# Sheet1.net
KiCad netlist of a schematic drawn in Altium Designer
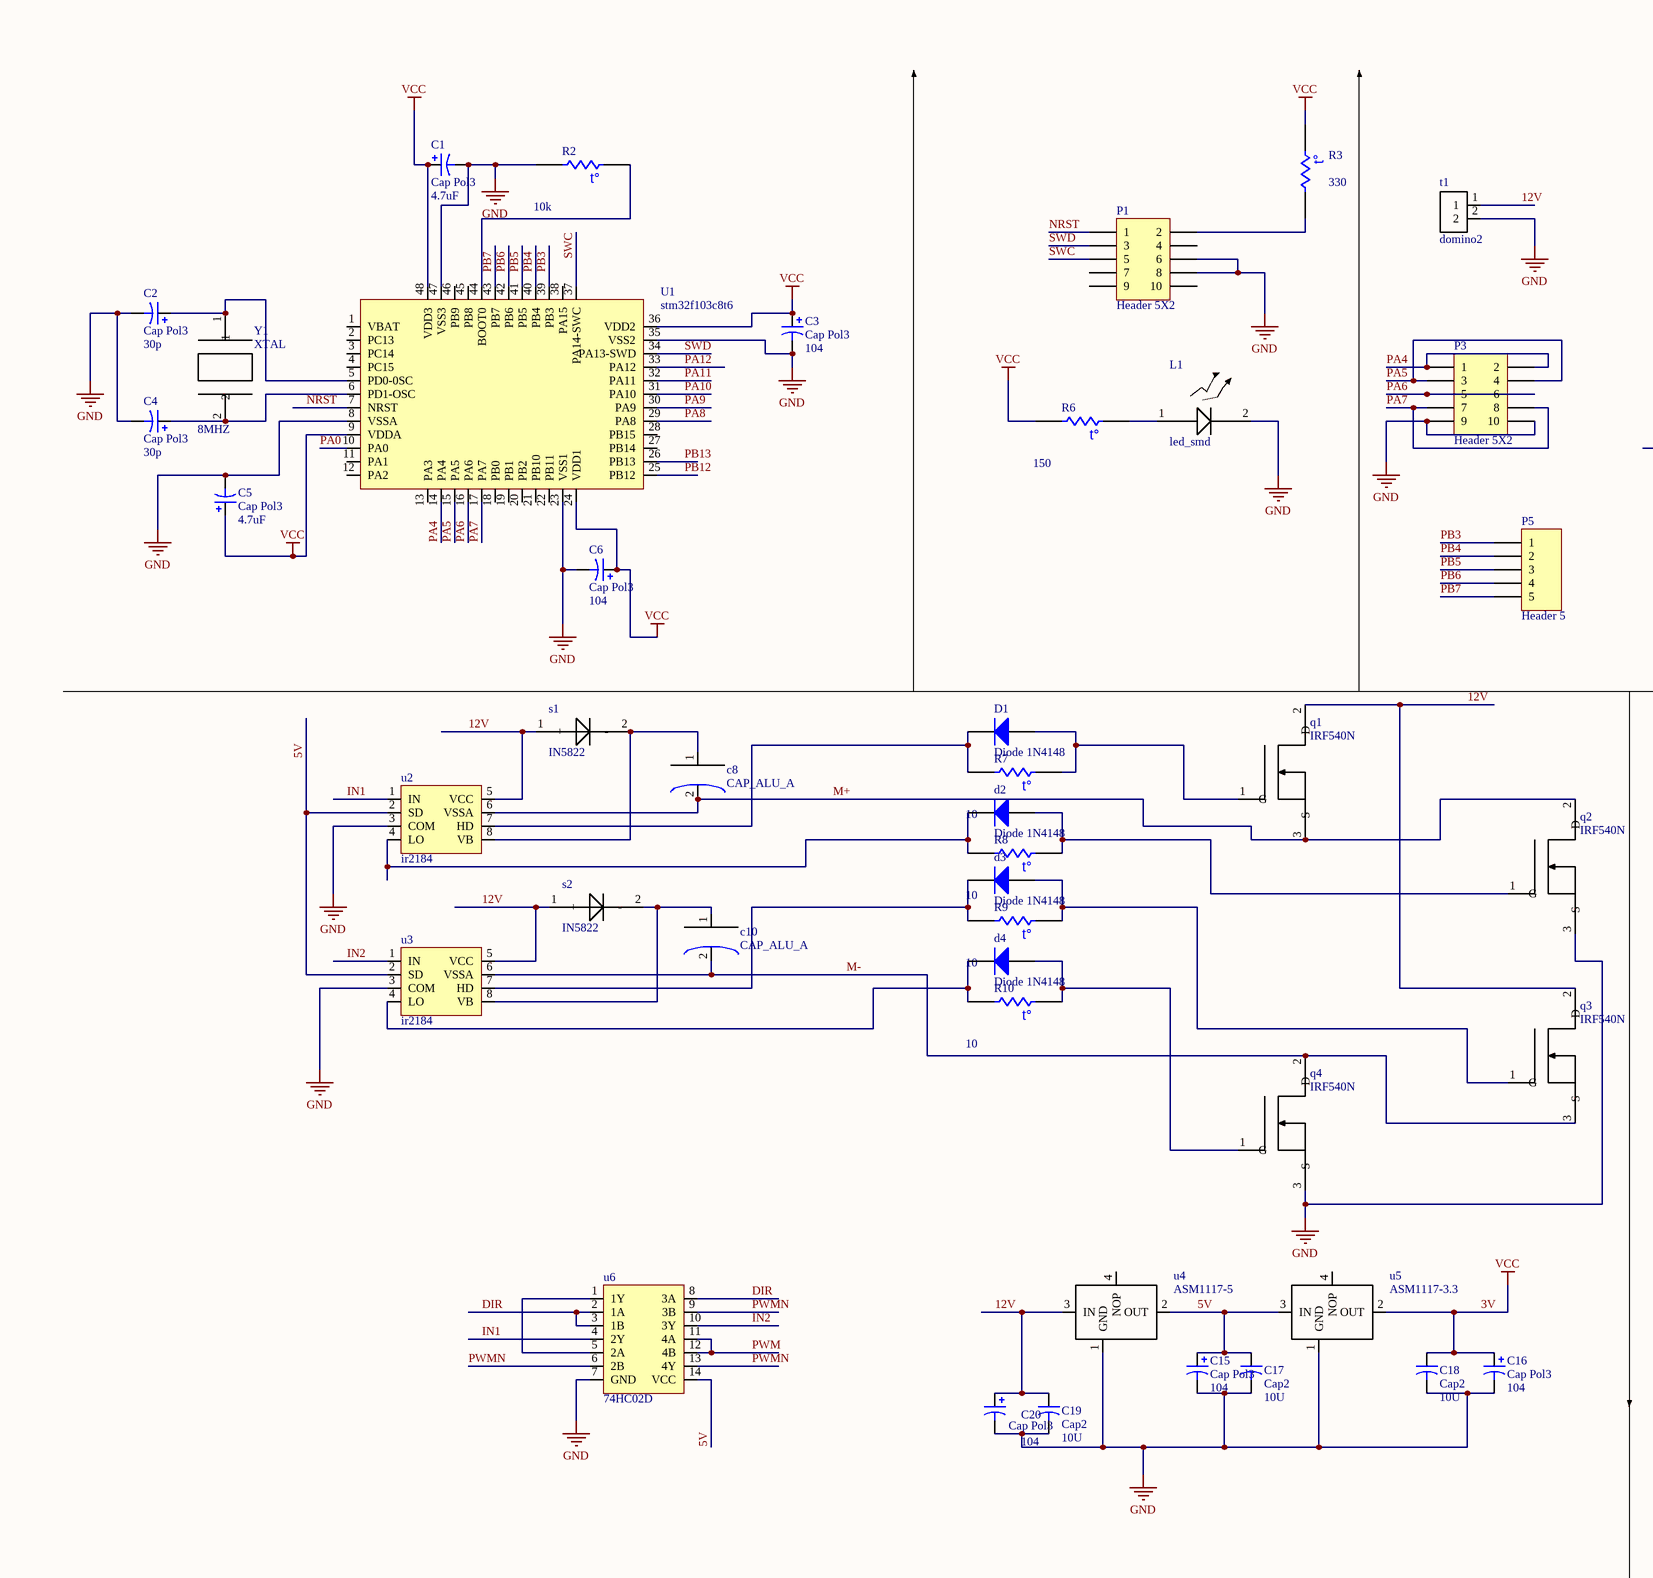
[diagram p0: Sheet1.SchDoc, left]
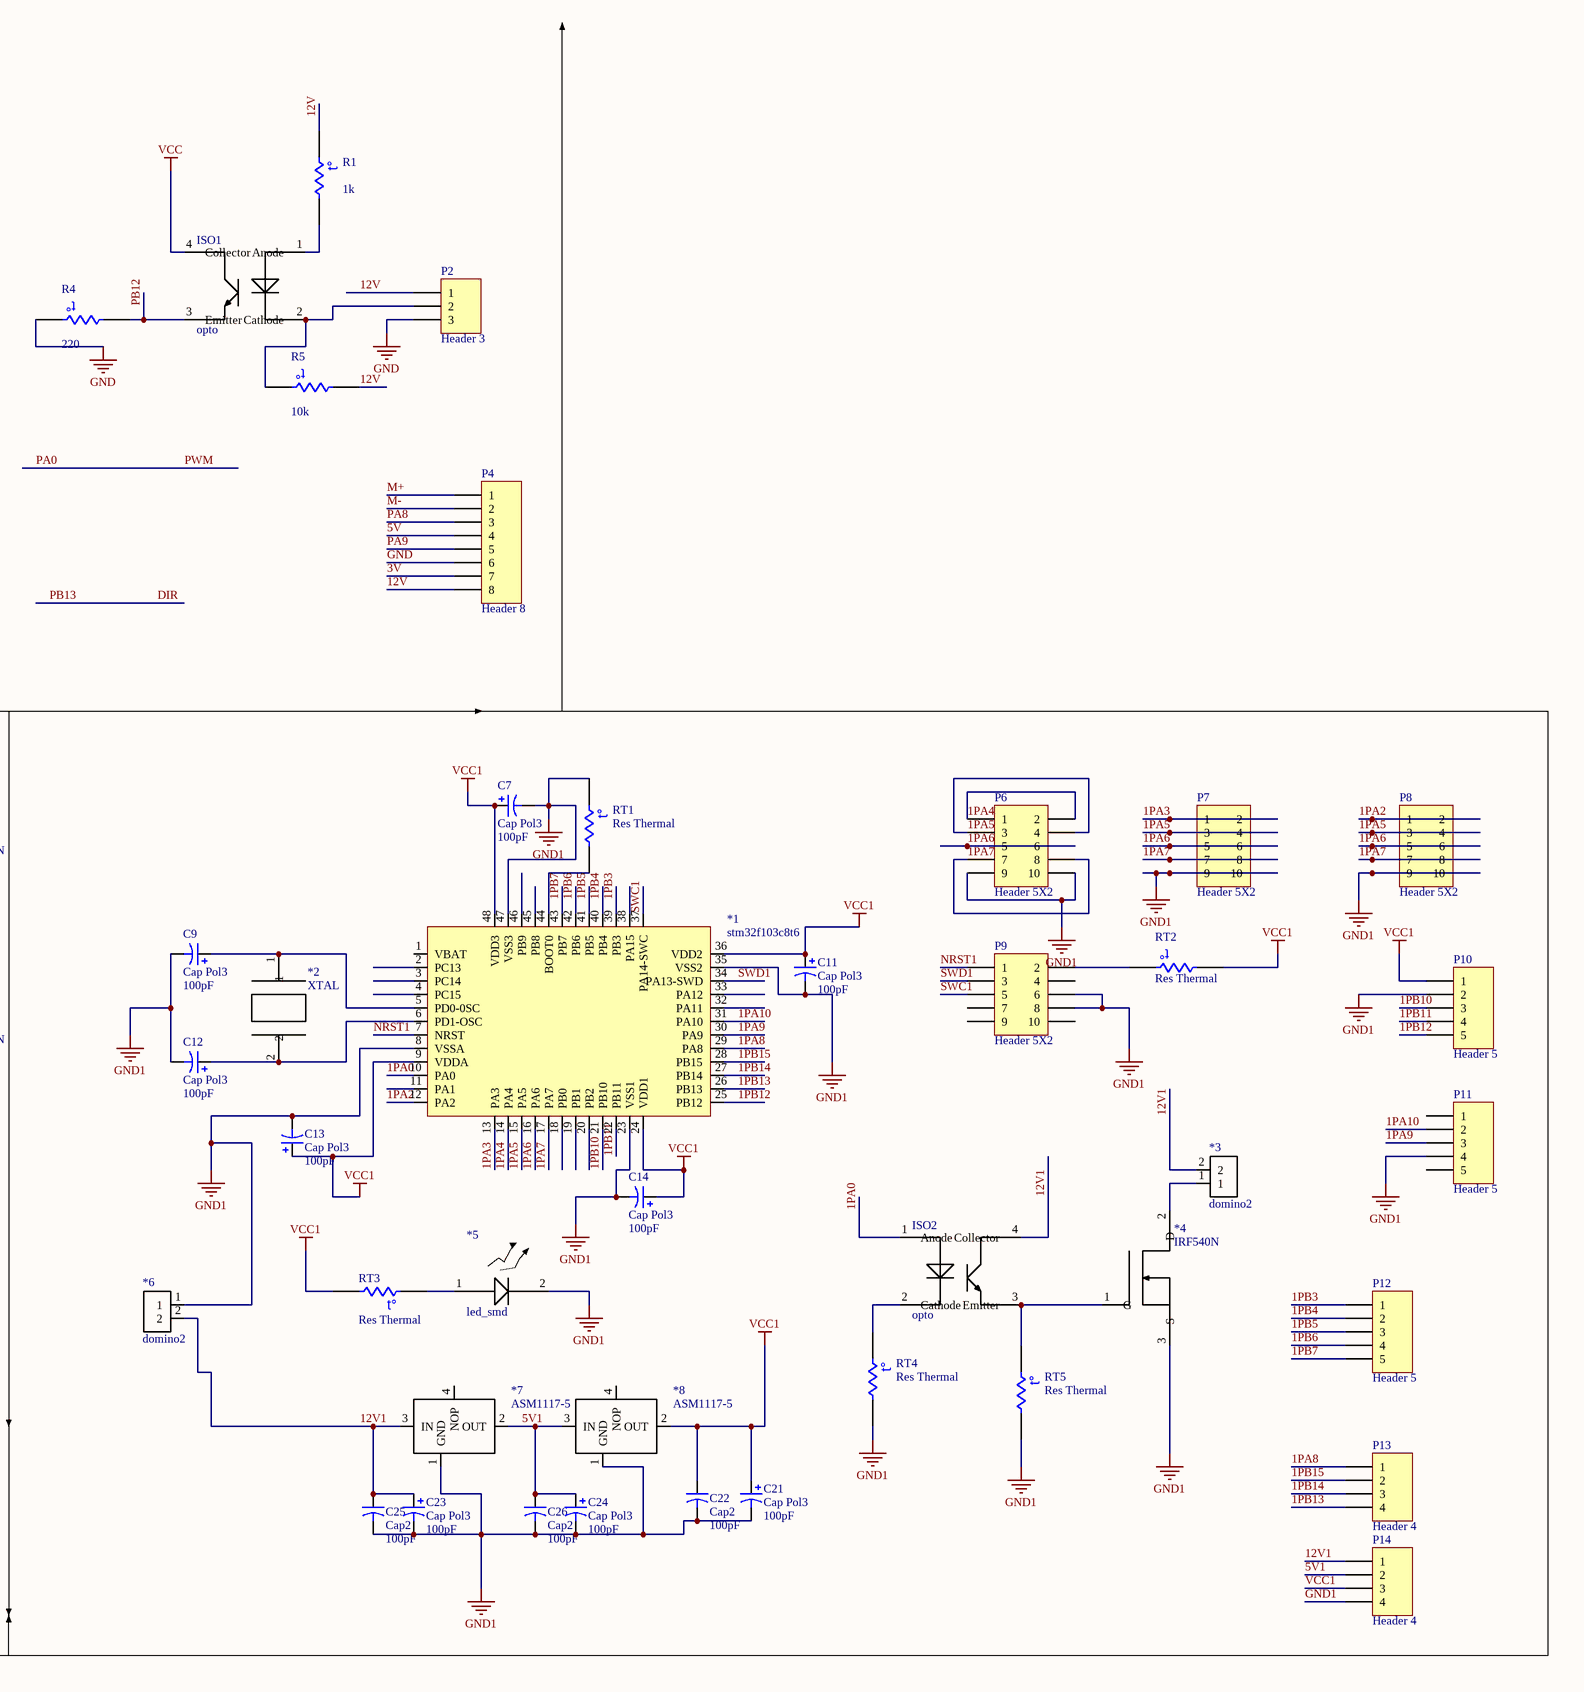
[diagram p1: Sheet1.SchDoc, right]

(export (version "E")
  (design (tool "Eeschema 10.0.6"))
  (components
    (comp (ref "*1")
      (value "stm32f103c8t6")
      (footprint "Pcbforslave:LQFP48_stm32")
      (libsource (lib "Schlib1") (part "stm32f103c8t6"))
    )
    (comp (ref "*2")
      (value "XTAL")
      (footprint "Pcbforslave:xtal_smd")
      (libsource (lib "Schlib1") (part "XTAL"))
    )
    (comp (ref "*3")
      (value "domino2")
      (footprint "Pcbforslave:Domino_2")
      (libsource (lib "Schlib1") (part "domino2"))
    )
    (comp (ref "*4")
      (value "IRF540N")
      (footprint "Pcbforslave:TO220")
      (libsource (lib "Schlib1") (part "IRF540N"))
    )
    (comp (ref "*5")
      (value "led_smd")
      (footprint "Pcbforslave:led_smd")
      (libsource (lib "Schlib1") (part "led_smd"))
    )
    (comp (ref "*6")
      (value "domino2")
      (footprint "Pcbforslave:Domino_2")
      (libsource (lib "Schlib1") (part "domino2"))
    )
    (comp (ref "*7")
      (value "ASM1117-5")
      (footprint "Pcbforslave:SOT223")
      (libsource (lib "Schlib1") (part "ASM1117-5"))
    )
    (comp (ref "*8")
      (value "ASM1117-5")
      (footprint "Pcbforslave:SOT223")
      (libsource (lib "Schlib1") (part "ASM1117-5"))
    )
    (comp (ref "C1")
      (value "Cap Pol3")
      (footprint "C0805")
      (description "Polarized Capacitor (Surface Mount)")
      (fields (field (name "ALTIUM_VALUE") "4.7uF"))
      (libsource (lib "Miscellaneous Devices") (part "Cap Pol3"))
    )
    (comp (ref "C2")
      (value "Cap Pol3")
      (footprint "C0805")
      (description "Polarized Capacitor (Surface Mount)")
      (fields (field (name "ALTIUM_VALUE") "30p"))
      (libsource (lib "Miscellaneous Devices") (part "Cap Pol3"))
    )
    (comp (ref "C3")
      (value "Cap Pol3")
      (footprint "C0805")
      (description "Polarized Capacitor (Surface Mount)")
      (fields (field (name "ALTIUM_VALUE") "104"))
      (libsource (lib "Miscellaneous Devices") (part "Cap Pol3"))
    )
    (comp (ref "C4")
      (value "Cap Pol3")
      (footprint "C0805")
      (description "Polarized Capacitor (Surface Mount)")
      (fields (field (name "ALTIUM_VALUE") "30p"))
      (libsource (lib "Miscellaneous Devices") (part "Cap Pol3"))
    )
    (comp (ref "C5")
      (value "Cap Pol3")
      (footprint "C0805")
      (description "Polarized Capacitor (Surface Mount)")
      (fields (field (name "ALTIUM_VALUE") "4.7uF"))
      (libsource (lib "Miscellaneous Devices") (part "Cap Pol3"))
    )
    (comp (ref "C6")
      (value "Cap Pol3")
      (footprint "C0805")
      (description "Polarized Capacitor (Surface Mount)")
      (fields (field (name "ALTIUM_VALUE") "104"))
      (libsource (lib "Miscellaneous Devices") (part "Cap Pol3"))
    )
    (comp (ref "C7")
      (value "Cap Pol3")
      (footprint "C0805")
      (description "Polarized Capacitor (Surface Mount)")
      (fields (field (name "ALTIUM_VALUE") "100pF"))
      (libsource (lib "Miscellaneous Devices") (part "Cap Pol3"))
    )
    (comp (ref "c8")
      (value "CAP_ALU_A")
      (footprint "cap_alu_a")
      (libsource (lib "Schlib1") (part "CAP_ALU_A"))
    )
    (comp (ref "C9")
      (value "Cap Pol3")
      (footprint "C0805")
      (description "Polarized Capacitor (Surface Mount)")
      (fields (field (name "ALTIUM_VALUE") "100pF"))
      (libsource (lib "Miscellaneous Devices") (part "Cap Pol3"))
    )
    (comp (ref "c10")
      (value "CAP_ALU_A")
      (footprint "cap_alu_a")
      (libsource (lib "Schlib1") (part "CAP_ALU_A"))
    )
    (comp (ref "C11")
      (value "Cap Pol3")
      (footprint "C0805")
      (description "Polarized Capacitor (Surface Mount)")
      (fields (field (name "ALTIUM_VALUE") "100pF"))
      (libsource (lib "Miscellaneous Devices") (part "Cap Pol3"))
    )
    (comp (ref "C12")
      (value "Cap Pol3")
      (footprint "C0805")
      (description "Polarized Capacitor (Surface Mount)")
      (fields (field (name "ALTIUM_VALUE") "100pF"))
      (libsource (lib "Miscellaneous Devices") (part "Cap Pol3"))
    )
    (comp (ref "C13")
      (value "Cap Pol3")
      (footprint "C0805")
      (description "Polarized Capacitor (Surface Mount)")
      (fields (field (name "ALTIUM_VALUE") "100pF"))
      (libsource (lib "Miscellaneous Devices") (part "Cap Pol3"))
    )
    (comp (ref "C14")
      (value "Cap Pol3")
      (footprint "C0805")
      (description "Polarized Capacitor (Surface Mount)")
      (fields (field (name "ALTIUM_VALUE") "100pF"))
      (libsource (lib "Miscellaneous Devices") (part "Cap Pol3"))
    )
    (comp (ref "C15")
      (value "Cap Pol3")
      (footprint "C0805")
      (description "Polarized Capacitor (Surface Mount)")
      (fields (field (name "ALTIUM_VALUE") "104"))
      (libsource (lib "Miscellaneous Devices") (part "Cap Pol3"))
    )
    (comp (ref "C16")
      (value "Cap Pol3")
      (footprint "C0805")
      (description "Polarized Capacitor (Surface Mount)")
      (fields (field (name "ALTIUM_VALUE") "104"))
      (libsource (lib "Miscellaneous Devices") (part "Cap Pol3"))
    )
    (comp (ref "C17")
      (value "Cap2")
      (footprint "CAPR5-4X5")
      (description "Capacitor")
      (fields (field (name "ALTIUM_VALUE") "10U"))
      (libsource (lib "Miscellaneous Devices") (part "Cap2"))
    )
    (comp (ref "C18")
      (value "Cap2")
      (footprint "CAPR5-4X5")
      (description "Capacitor")
      (fields (field (name "ALTIUM_VALUE") "10U"))
      (libsource (lib "Miscellaneous Devices") (part "Cap2"))
    )
    (comp (ref "C19")
      (value "Cap2")
      (footprint "CAPR5-4X5")
      (description "Capacitor")
      (fields (field (name "ALTIUM_VALUE") "10U"))
      (libsource (lib "Miscellaneous Devices") (part "Cap2"))
    )
    (comp (ref "C20")
      (value "Cap Pol3")
      (footprint "C0805")
      (description "Polarized Capacitor (Surface Mount)")
      (fields (field (name "ALTIUM_VALUE") "104"))
      (libsource (lib "Miscellaneous Devices") (part "Cap Pol3"))
    )
    (comp (ref "C21")
      (value "Cap Pol3")
      (footprint "C0805")
      (description "Polarized Capacitor (Surface Mount)")
      (fields (field (name "ALTIUM_VALUE") "100pF"))
      (libsource (lib "Miscellaneous Devices") (part "Cap Pol3"))
    )
    (comp (ref "C22")
      (value "Cap2")
      (footprint "CAPR5-4X5")
      (description "Capacitor")
      (fields (field (name "ALTIUM_VALUE") "100pF"))
      (libsource (lib "Miscellaneous Devices") (part "Cap2"))
    )
    (comp (ref "C23")
      (value "Cap Pol3")
      (footprint "C0805")
      (description "Polarized Capacitor (Surface Mount)")
      (fields (field (name "ALTIUM_VALUE") "100pF"))
      (libsource (lib "Miscellaneous Devices") (part "Cap Pol3"))
    )
    (comp (ref "C24")
      (value "Cap Pol3")
      (footprint "C0805")
      (description "Polarized Capacitor (Surface Mount)")
      (fields (field (name "ALTIUM_VALUE") "100pF"))
      (libsource (lib "Miscellaneous Devices") (part "Cap Pol3"))
    )
    (comp (ref "C25")
      (value "Cap2")
      (footprint "CAPR5-4X5")
      (description "Capacitor")
      (fields (field (name "ALTIUM_VALUE") "100pF"))
      (libsource (lib "Miscellaneous Devices") (part "Cap2"))
    )
    (comp (ref "C26")
      (value "Cap2")
      (footprint "CAPR5-4X5")
      (description "Capacitor")
      (fields (field (name "ALTIUM_VALUE") "100pF"))
      (libsource (lib "Miscellaneous Devices") (part "Cap2"))
    )
    (comp (ref "D1")
      (value "Diode 1N4148")
      (footprint "DO-35")
      (description "High Conductance Fast Diode")
      (libsource (lib "Miscellaneous Devices") (part "Diode 1N4148"))
    )
    (comp (ref "d2")
      (value "Diode 1N4148")
      (footprint "DO-35")
      (description "High Conductance Fast Diode")
      (libsource (lib "Miscellaneous Devices") (part "Diode 1N4148"))
    )
    (comp (ref "d3")
      (value "Diode 1N4148")
      (footprint "DO-35")
      (description "High Conductance Fast Diode")
      (libsource (lib "Miscellaneous Devices") (part "Diode 1N4148"))
    )
    (comp (ref "d4")
      (value "Diode 1N4148")
      (footprint "DO-35")
      (description "High Conductance Fast Diode")
      (libsource (lib "Miscellaneous Devices") (part "Diode 1N4148"))
    )
    (comp (ref "ISO1")
      (value "opto")
      (footprint "Pcbforslave:opto_smd")
      (libsource (lib "Schlib1") (part "opto"))
    )
    (comp (ref "ISO2")
      (value "opto")
      (footprint "Pcbforslave:opto_smd")
      (libsource (lib "Schlib1") (part "opto"))
    )
    (comp (ref "L1") (value "led_smd") (footprint "led_smd") (libsource (lib "Schlib1") (part "led_smd")))
    (comp (ref "P1")
      (value "Header 5X2")
      (footprint "HDR2X5")
      (description "Header, 5-Pin, Dual row")
      (libsource (lib "Miscellaneous Connectors") (part "Header 5X2"))
    )
    (comp (ref "P2")
      (value "Header 3")
      (footprint "HDR1X3")
      (description "Header, 3-Pin")
      (libsource (lib "Miscellaneous Connectors") (part "Header 3"))
    )
    (comp (ref "P3")
      (value "Header 5X2")
      (footprint "HDR2X5")
      (description "Header, 5-Pin, Dual row")
      (libsource (lib "Miscellaneous Connectors") (part "Header 5X2"))
    )
    (comp (ref "P4")
      (value "Header 8")
      (footprint "HDR1X8")
      (description "Header, 8-Pin")
      (libsource (lib "Miscellaneous Connectors") (part "Header 8"))
    )
    (comp (ref "P5")
      (value "Header 5")
      (footprint "HDR1X5")
      (description "Header, 5-Pin")
      (libsource (lib "Miscellaneous Connectors") (part "Header 5"))
    )
    (comp (ref "P6")
      (value "Header 5X2")
      (footprint "HDR2X5")
      (description "Header, 5-Pin, Dual row")
      (libsource (lib "Miscellaneous Connectors") (part "Header 5X2"))
    )
    (comp (ref "P7")
      (value "Header 5X2")
      (footprint "HDR2X5")
      (description "Header, 5-Pin, Dual row")
      (libsource (lib "Miscellaneous Connectors") (part "Header 5X2"))
    )
    (comp (ref "P8")
      (value "Header 5X2")
      (footprint "HDR2X5")
      (description "Header, 5-Pin, Dual row")
      (libsource (lib "Miscellaneous Connectors") (part "Header 5X2"))
    )
    (comp (ref "P9")
      (value "Header 5X2")
      (footprint "HDR2X5")
      (description "Header, 5-Pin, Dual row")
      (libsource (lib "Miscellaneous Connectors") (part "Header 5X2"))
    )
    (comp (ref "P10")
      (value "Header 5")
      (footprint "HDR1X5")
      (description "Header, 5-Pin")
      (libsource (lib "Miscellaneous Connectors") (part "Header 5"))
    )
    (comp (ref "P11")
      (value "Header 5")
      (footprint "HDR1X5")
      (description "Header, 5-Pin")
      (libsource (lib "Miscellaneous Connectors") (part "Header 5"))
    )
    (comp (ref "P12")
      (value "Header 5")
      (footprint "HDR1X5")
      (description "Header, 5-Pin")
      (libsource (lib "Miscellaneous Connectors") (part "Header 5"))
    )
    (comp (ref "P13")
      (value "Header 4")
      (footprint "HDR1X4")
      (description "Header, 4-Pin")
      (libsource (lib "Miscellaneous Connectors") (part "Header 4"))
    )
    (comp (ref "P14")
      (value "Header 4")
      (footprint "HDR1X4")
      (description "Header, 4-Pin")
      (libsource (lib "Miscellaneous Connectors") (part "Header 4"))
    )
    (comp (ref "q1") (value "IRF540N") (footprint "TO220") (libsource (lib "Schlib1") (part "IRF540N")))
    (comp (ref "q2") (value "IRF540N") (footprint "TO220") (libsource (lib "Schlib1") (part "IRF540N")))
    (comp (ref "q3") (value "IRF540N") (footprint "TO220") (libsource (lib "Schlib1") (part "IRF540N")))
    (comp (ref "q4") (value "IRF540N") (footprint "TO220") (libsource (lib "Schlib1") (part "IRF540N")))
    (comp (ref "R1")
      (value "1k")
      (footprint "6-0805_N")
      (description "Thermistor")
      (libsource (lib "Miscellaneous Devices") (part "Res Thermal"))
    )
    (comp (ref "R2")
      (value "10k")
      (footprint "6-0805_N")
      (description "Thermistor")
      (libsource (lib "Miscellaneous Devices") (part "Res Thermal"))
    )
    (comp (ref "R3")
      (value "330")
      (footprint "6-0805_N")
      (description "Thermistor")
      (libsource (lib "Miscellaneous Devices") (part "Res Thermal"))
    )
    (comp (ref "R4")
      (value "220")
      (footprint "6-0805_N")
      (description "Thermistor")
      (libsource (lib "Miscellaneous Devices") (part "Res Thermal"))
    )
    (comp (ref "R5")
      (value "10k")
      (footprint "6-0805_N")
      (description "Thermistor")
      (libsource (lib "Miscellaneous Devices") (part "Res Thermal"))
    )
    (comp (ref "R6")
      (value "150")
      (footprint "6-0805_N")
      (description "Thermistor")
      (libsource (lib "Miscellaneous Devices") (part "Res Thermal"))
    )
    (comp (ref "R7")
      (value "10")
      (footprint "6-0805_N")
      (description "Thermistor")
      (libsource (lib "Miscellaneous Devices") (part "Res Thermal"))
    )
    (comp (ref "R8")
      (value "10")
      (footprint "6-0805_N")
      (description "Thermistor")
      (libsource (lib "Miscellaneous Devices") (part "Res Thermal"))
    )
    (comp (ref "R9")
      (value "10")
      (footprint "6-0805_N")
      (description "Thermistor")
      (libsource (lib "Miscellaneous Devices") (part "Res Thermal"))
    )
    (comp (ref "R10")
      (value "10")
      (footprint "6-0805_N")
      (description "Thermistor")
      (libsource (lib "Miscellaneous Devices") (part "Res Thermal"))
    )
    (comp (ref "RT1")
      (value "Res Thermal")
      (footprint "6-0805_N")
      (description "Thermistor")
      (libsource (lib "Miscellaneous Devices") (part "Res Thermal"))
    )
    (comp (ref "RT2")
      (value "Res Thermal")
      (footprint "6-0805_N")
      (description "Thermistor")
      (libsource (lib "Miscellaneous Devices") (part "Res Thermal"))
    )
    (comp (ref "RT3")
      (value "Res Thermal")
      (footprint "6-0805_N")
      (description "Thermistor")
      (libsource (lib "Miscellaneous Devices") (part "Res Thermal"))
    )
    (comp (ref "RT4")
      (value "Res Thermal")
      (footprint "6-0805_N")
      (description "Thermistor")
      (libsource (lib "Miscellaneous Devices") (part "Res Thermal"))
    )
    (comp (ref "RT5")
      (value "Res Thermal")
      (footprint "6-0805_N")
      (description "Thermistor")
      (libsource (lib "Miscellaneous Devices") (part "Res Thermal"))
    )
    (comp (ref "s1")
      (value "IN5822")
      (footprint "schottky diode")
      (libsource (lib "Schlib1") (part "IN5822"))
    )
    (comp (ref "s2")
      (value "IN5822")
      (footprint "schottky diode")
      (libsource (lib "Schlib1") (part "IN5822"))
    )
    (comp (ref "t1") (value "domino2") (footprint "Domino_2") (libsource (lib "Schlib1") (part "domino2")))
    (comp (ref "U1")
      (value "stm32f103c8t6")
      (footprint "Pcbforslave:LQFP48_stm32")
      (libsource (lib "Schlib1") (part "stm32f103c8t6"))
    )
    (comp (ref "u2") (value "ir2184") (footprint "SOP8_ir2184") (libsource (lib "Schlib1") (part "ir2184")))
    (comp (ref "u3") (value "ir2184") (footprint "SOP8_ir2184") (libsource (lib "Schlib1") (part "ir2184")))
    (comp (ref "u4") (value "ASM1117-5") (footprint "SOT223") (libsource (lib "Schlib1") (part "ASM1117-5")))
    (comp (ref "u5")
      (value "ASM1117-3.3")
      (footprint "SOT223")
      (libsource (lib "Schlib1") (part "ASM1117-5"))
    )
    (comp (ref "u6")
      (value "74HC02D")
      (footprint "SOP14_Nor gate")
      (libsource (lib "Schlib1") (part "74HC02D"))
    )
    (comp (ref "Y1")
      (value "XTAL")
      (footprint "xtal_smd")
      (fields (field (name "ALTIUM_VALUE") "8MHZ"))
      (libsource (lib "Schlib1") (part "XTAL"))
    )
  )
  (nets
    (net (code "1") (name "/1PA0") (class "Default")
      (node (ref "*1") (pin "10") (pinfunction "PA0_10") (pintype "passive"))
      (node (ref "ISO2") (pin "1") (pinfunction "Anode_1") (pintype "passive"))
    )
    (net (code "2") (name "/1PA2") (class "Default")
      (node (ref "*1") (pin "12") (pinfunction "PA2_12") (pintype "passive"))
      (node (ref "P8") (pin "1") (pinfunction "1_1") (pintype "passive"))
      (node (ref "P8") (pin "2") (pinfunction "2_2") (pintype "passive"))
    )
    (net (code "3") (name "/1PA3") (class "Default")
      (node (ref "*1") (pin "13") (pinfunction "PA3_13") (pintype "passive"))
      (node (ref "P7") (pin "1") (pinfunction "1_1") (pintype "passive"))
      (node (ref "P7") (pin "2") (pinfunction "2_2") (pintype "passive"))
    )
    (net (code "4") (name "/1PA4") (class "Default")
      (node (ref "*1") (pin "14") (pinfunction "PA4_14") (pintype "passive"))
      (node (ref "P6") (pin "1") (pinfunction "1_1") (pintype "passive"))
      (node (ref "P6") (pin "2") (pinfunction "2_2") (pintype "passive"))
    )
    (net (code "5") (name "/1PA5") (class "Default")
      (node (ref "*1") (pin "15") (pinfunction "PA5_15") (pintype "passive"))
      (node (ref "P6") (pin "3") (pinfunction "3_3") (pintype "passive"))
      (node (ref "P6") (pin "4") (pinfunction "4_4") (pintype "passive"))
      (node (ref "P7") (pin "3") (pinfunction "3_3") (pintype "passive"))
      (node (ref "P7") (pin "4") (pinfunction "4_4") (pintype "passive"))
      (node (ref "P8") (pin "3") (pinfunction "3_3") (pintype "passive"))
      (node (ref "P8") (pin "4") (pinfunction "4_4") (pintype "passive"))
    )
    (net (code "6") (name "/1PA6") (class "Default")
      (node (ref "*1") (pin "16") (pinfunction "PA6_16") (pintype "passive"))
      (node (ref "P6") (pin "5") (pinfunction "5_5") (pintype "passive"))
      (node (ref "P6") (pin "6") (pinfunction "6_6") (pintype "passive"))
      (node (ref "P7") (pin "5") (pinfunction "5_5") (pintype "passive"))
      (node (ref "P7") (pin "6") (pinfunction "6_6") (pintype "passive"))
      (node (ref "P8") (pin "5") (pinfunction "5_5") (pintype "passive"))
      (node (ref "P8") (pin "6") (pinfunction "6_6") (pintype "passive"))
    )
    (net (code "7") (name "/1PA7") (class "Default")
      (node (ref "*1") (pin "17") (pinfunction "PA7_17") (pintype "passive"))
      (node (ref "P6") (pin "7") (pinfunction "7_7") (pintype "passive"))
      (node (ref "P6") (pin "8") (pinfunction "8_8") (pintype "passive"))
      (node (ref "P7") (pin "7") (pinfunction "7_7") (pintype "passive"))
      (node (ref "P7") (pin "8") (pinfunction "8_8") (pintype "passive"))
      (node (ref "P8") (pin "7") (pinfunction "7_7") (pintype "passive"))
      (node (ref "P8") (pin "8") (pinfunction "8_8") (pintype "passive"))
    )
    (net (code "8") (name "/1PA8") (class "Default")
      (node (ref "*1") (pin "29") (pinfunction "PA8_29") (pintype "passive"))
      (node (ref "P13") (pin "1") (pinfunction "1_1") (pintype "passive"))
    )
    (net (code "9") (name "/1PA9") (class "Default")
      (node (ref "*1") (pin "30") (pinfunction "PA9_30") (pintype "passive"))
      (node (ref "P11") (pin "3") (pinfunction "3_3") (pintype "passive"))
    )
    (net (code "10") (name "/1PA10") (class "Default")
      (node (ref "*1") (pin "31") (pinfunction "PA10_31") (pintype "passive"))
      (node (ref "P11") (pin "2") (pinfunction "2_2") (pintype "passive"))
    )
    (net (code "11") (name "/1PB3") (class "Default")
      (node (ref "*1") (pin "39") (pinfunction "PB3_39") (pintype "passive"))
      (node (ref "P12") (pin "1") (pinfunction "1_1") (pintype "passive"))
    )
    (net (code "12") (name "/1PB4") (class "Default")
      (node (ref "*1") (pin "40") (pinfunction "PB4_40") (pintype "passive"))
      (node (ref "P12") (pin "2") (pinfunction "2_2") (pintype "passive"))
    )
    (net (code "13") (name "/1PB5") (class "Default")
      (node (ref "*1") (pin "41") (pinfunction "PB5_41") (pintype "passive"))
      (node (ref "P12") (pin "3") (pinfunction "3_3") (pintype "passive"))
    )
    (net (code "14") (name "/1PB6") (class "Default")
      (node (ref "*1") (pin "42") (pinfunction "PB6_42") (pintype "passive"))
      (node (ref "P12") (pin "4") (pinfunction "4_4") (pintype "passive"))
    )
    (net (code "15") (name "/1PB7") (class "Default")
      (node (ref "*1") (pin "43") (pinfunction "PB7_43") (pintype "passive"))
      (node (ref "P12") (pin "5") (pinfunction "5_5") (pintype "passive"))
    )
    (net (code "16") (name "/1PB10") (class "Default")
      (node (ref "*1") (pin "21") (pinfunction "PB10_21") (pintype "passive"))
      (node (ref "P10") (pin "3") (pinfunction "3_3") (pintype "passive"))
    )
    (net (code "17") (name "/1PB11") (class "Default")
      (node (ref "*1") (pin "22") (pinfunction "PB11_22") (pintype "passive"))
      (node (ref "P10") (pin "4") (pinfunction "4_4") (pintype "passive"))
    )
    (net (code "18") (name "/1PB12") (class "Default")
      (node (ref "*1") (pin "25") (pinfunction "PB12_25") (pintype "passive"))
      (node (ref "P10") (pin "5") (pinfunction "5_5") (pintype "passive"))
    )
    (net (code "19") (name "/1PB13") (class "Default")
      (node (ref "*1") (pin "26") (pinfunction "PB13_26") (pintype "passive"))
      (node (ref "P13") (pin "4") (pinfunction "4_4") (pintype "passive"))
    )
    (net (code "20") (name "/1PB14") (class "Default")
      (node (ref "*1") (pin "27") (pinfunction "PB14_27") (pintype "passive"))
      (node (ref "P13") (pin "3") (pinfunction "3_3") (pintype "passive"))
    )
    (net (code "21") (name "/1PB15") (class "Default")
      (node (ref "*1") (pin "28") (pinfunction "PB15_28") (pintype "passive"))
      (node (ref "P13") (pin "2") (pinfunction "2_2") (pintype "passive"))
    )
    (net (code "22") (name "/5V") (class "Default")
      (node (ref "C15") (pin "1") (pinfunction "1_1") (pintype "passive"))
      (node (ref "C17") (pin "1") (pinfunction "1_1") (pintype "passive"))
      (node (ref "P4") (pin "4") (pinfunction "4_4") (pintype "passive"))
      (node (ref "u2") (pin "2") (pinfunction "SD_2") (pintype "passive"))
      (node (ref "u3") (pin "2") (pinfunction "SD_2") (pintype "passive"))
      (node (ref "u4") (pin "2") (pinfunction "OUT_2") (pintype "passive"))
      (node (ref "u5") (pin "3") (pinfunction "IN_3") (pintype "passive"))
      (node (ref "u6") (pin "14") (pinfunction "VCC_14") (pintype "passive"))
    )
    (net (code "23") (name "/5V1") (class "Default")
      (node (ref "*7") (pin "2") (pinfunction "OUT_2") (pintype "passive"))
      (node (ref "*8") (pin "3") (pinfunction "IN_3") (pintype "passive"))
      (node (ref "C24") (pin "1") (pinfunction "1_1") (pintype "passive"))
      (node (ref "C26") (pin "1") (pinfunction "1_1") (pintype "passive"))
      (node (ref "P14") (pin "2") (pinfunction "2_2") (pintype "passive"))
    )
    (net (code "24") (name "/12V") (class "Default")
      (node (ref "C19") (pin "1") (pinfunction "1_1") (pintype "passive"))
      (node (ref "C20") (pin "1") (pinfunction "1_1") (pintype "passive"))
      (node (ref "P2") (pin "1") (pinfunction "1_1") (pintype "passive"))
      (node (ref "P4") (pin "8") (pinfunction "8_8") (pintype "passive"))
      (node (ref "R1") (pin "1") (pinfunction "1_1") (pintype "passive"))
      (node (ref "R5") (pin "2") (pinfunction "2_2") (pintype "passive"))
      (node (ref "q1") (pin "2") (pinfunction "D_2") (pintype "passive"))
      (node (ref "q3") (pin "2") (pinfunction "D_2") (pintype "passive"))
      (node (ref "s1") (pin "1") (pinfunction "+_1") (pintype "passive"))
      (node (ref "s2") (pin "1") (pinfunction "+_1") (pintype "passive"))
      (node (ref "t1") (pin "1") (pinfunction "1_1") (pintype "passive"))
      (node (ref "u2") (pin "5") (pinfunction "VCC_5") (pintype "passive"))
      (node (ref "u3") (pin "5") (pinfunction "VCC_5") (pintype "passive"))
      (node (ref "u4") (pin "3") (pinfunction "IN_3") (pintype "passive"))
    )
    (net (code "25") (name "/12V1") (class "Default")
      (node (ref "*3") (pin "2") (pinfunction "2_2") (pintype "passive"))
      (node (ref "*6") (pin "2") (pinfunction "2_2") (pintype "passive"))
      (node (ref "*7") (pin "3") (pinfunction "IN_3") (pintype "passive"))
      (node (ref "C23") (pin "1") (pinfunction "1_1") (pintype "passive"))
      (node (ref "C25") (pin "1") (pinfunction "1_1") (pintype "passive"))
      (node (ref "ISO2") (pin "4") (pinfunction "Collector_4") (pintype "passive"))
      (node (ref "P14") (pin "1") (pinfunction "1_1") (pintype "passive"))
    )
    (net (code "26") (name "/DIR") (class "Default")
      (node (ref "U1") (pin "26") (pinfunction "PB13_26") (pintype "passive"))
      (node (ref "u6") (pin "2") (pinfunction "1A_2") (pintype "passive"))
      (node (ref "u6") (pin "3") (pinfunction "1B_3") (pintype "passive"))
      (node (ref "u6") (pin "8") (pinfunction "3A_8") (pintype "passive"))
    )
    (net (code "27") (name "/IN1") (class "Default")
      (node (ref "u2") (pin "1") (pinfunction "IN_1") (pintype "passive"))
      (node (ref "u6") (pin "4") (pinfunction "2Y_4") (pintype "passive"))
    )
    (net (code "28") (name "/IN2") (class "Default")
      (node (ref "u3") (pin "1") (pinfunction "IN_1") (pintype "passive"))
      (node (ref "u6") (pin "10") (pinfunction "3Y_10") (pintype "passive"))
    )
    (net (code "29") (name "/M+") (class "Default")
      (node (ref "P4") (pin "1") (pinfunction "1_1") (pintype "passive"))
      (node (ref "c8") (pin "2") (pinfunction "-_2") (pintype "passive"))
      (node (ref "q1") (pin "3") (pinfunction "S_3") (pintype "passive"))
      (node (ref "q2") (pin "2") (pinfunction "D_2") (pintype "passive"))
      (node (ref "u2") (pin "6") (pinfunction "VSSA_6") (pintype "passive"))
    )
    (net (code "30") (name "/M-") (class "Default")
      (node (ref "P4") (pin "2") (pinfunction "2_2") (pintype "passive"))
      (node (ref "c10") (pin "2") (pinfunction "-_2") (pintype "passive"))
      (node (ref "q3") (pin "3") (pinfunction "S_3") (pintype "passive"))
      (node (ref "q4") (pin "2") (pinfunction "D_2") (pintype "passive"))
      (node (ref "u3") (pin "6") (pinfunction "VSSA_6") (pintype "passive"))
    )
    (net (code "31") (name "/NRST") (class "Default")
      (node (ref "P1") (pin "1") (pinfunction "1_1") (pintype "passive"))
      (node (ref "U1") (pin "7") (pinfunction "NRST_7") (pintype "passive"))
    )
    (net (code "32") (name "/NRST1") (class "Default")
      (node (ref "*1") (pin "7") (pinfunction "NRST_7") (pintype "passive"))
      (node (ref "P9") (pin "1") (pinfunction "1_1") (pintype "passive"))
    )
    (net (code "33") (name "/PA0") (class "Default")
      (node (ref "U1") (pin "10") (pinfunction "PA0_10") (pintype "passive"))
      (node (ref "u6") (pin "11") (pinfunction "4A_11") (pintype "passive"))
      (node (ref "u6") (pin "12") (pinfunction "4B_12") (pintype "passive"))
    )
    (net (code "34") (name "/PA4") (class "Default")
      (node (ref "P3") (pin "1") (pinfunction "1_1") (pintype "passive"))
      (node (ref "P3") (pin "2") (pinfunction "2_2") (pintype "passive"))
      (node (ref "U1") (pin "14") (pinfunction "PA4_14") (pintype "passive"))
    )
    (net (code "35") (name "/PA5") (class "Default")
      (node (ref "P3") (pin "3") (pinfunction "3_3") (pintype "passive"))
      (node (ref "P3") (pin "4") (pinfunction "4_4") (pintype "passive"))
      (node (ref "U1") (pin "15") (pinfunction "PA5_15") (pintype "passive"))
    )
    (net (code "36") (name "/PA6") (class "Default")
      (node (ref "P3") (pin "5") (pinfunction "5_5") (pintype "passive"))
      (node (ref "P3") (pin "6") (pinfunction "6_6") (pintype "passive"))
      (node (ref "U1") (pin "16") (pinfunction "PA6_16") (pintype "passive"))
    )
    (net (code "37") (name "/PA7") (class "Default")
      (node (ref "P3") (pin "7") (pinfunction "7_7") (pintype "passive"))
      (node (ref "P3") (pin "8") (pinfunction "8_8") (pintype "passive"))
      (node (ref "U1") (pin "17") (pinfunction "PA7_17") (pintype "passive"))
    )
    (net (code "38") (name "/PA8") (class "Default")
      (node (ref "P4") (pin "3") (pinfunction "3_3") (pintype "passive"))
      (node (ref "U1") (pin "29") (pinfunction "PA8_29") (pintype "passive"))
    )
    (net (code "39") (name "/PA9") (class "Default")
      (node (ref "P4") (pin "5") (pinfunction "5_5") (pintype "passive"))
      (node (ref "U1") (pin "30") (pinfunction "PA9_30") (pintype "passive"))
    )
    (net (code "40") (name "/PA10") (class "Default")
      (node (ref "U1") (pin "31") (pinfunction "PA10_31") (pintype "passive"))
    )
    (net (code "41") (name "/PA11") (class "Default")
      (node (ref "U1") (pin "32") (pinfunction "PA11_32") (pintype "passive"))
    )
    (net (code "42") (name "/PA12") (class "Default")
      (node (ref "U1") (pin "33") (pinfunction "PA12_33") (pintype "passive"))
    )
    (net (code "43") (name "/PB3") (class "Default")
      (node (ref "P5") (pin "1") (pinfunction "1_1") (pintype "passive"))
      (node (ref "U1") (pin "39") (pinfunction "PB3_39") (pintype "passive"))
    )
    (net (code "44") (name "/PB4") (class "Default")
      (node (ref "P5") (pin "2") (pinfunction "2_2") (pintype "passive"))
      (node (ref "U1") (pin "40") (pinfunction "PB4_40") (pintype "passive"))
    )
    (net (code "45") (name "/PB5") (class "Default")
      (node (ref "P5") (pin "3") (pinfunction "3_3") (pintype "passive"))
      (node (ref "U1") (pin "41") (pinfunction "PB5_41") (pintype "passive"))
    )
    (net (code "46") (name "/PB6") (class "Default")
      (node (ref "P5") (pin "4") (pinfunction "4_4") (pintype "passive"))
      (node (ref "U1") (pin "42") (pinfunction "PB6_42") (pintype "passive"))
    )
    (net (code "47") (name "/PB7") (class "Default")
      (node (ref "P5") (pin "5") (pinfunction "5_5") (pintype "passive"))
      (node (ref "U1") (pin "43") (pinfunction "PB7_43") (pintype "passive"))
    )
    (net (code "48") (name "/PB12") (class "Default")
      (node (ref "ISO1") (pin "3") (pinfunction "Emitter_3") (pintype "passive"))
      (node (ref "R4") (pin "2") (pinfunction "2_2") (pintype "passive"))
      (node (ref "U1") (pin "25") (pinfunction "PB12_25") (pintype "passive"))
    )
    (net (code "49") (name "/PWMN") (class "Default")
      (node (ref "u6") (pin "13") (pinfunction "4Y_13") (pintype "passive"))
      (node (ref "u6") (pin "6") (pinfunction "2B_6") (pintype "passive"))
      (node (ref "u6") (pin "9") (pinfunction "3B_9") (pintype "passive"))
    )
    (net (code "50") (name "/SWC") (class "Default")
      (node (ref "P1") (pin "5") (pinfunction "5_5") (pintype "passive"))
      (node (ref "U1") (pin "37") (pinfunction "PA14-SWC_37") (pintype "passive"))
    )
    (net (code "51") (name "/SWC1") (class "Default")
      (node (ref "*1") (pin "37") (pinfunction "PA14-SWC_37") (pintype "passive"))
      (node (ref "P9") (pin "5") (pinfunction "5_5") (pintype "passive"))
    )
    (net (code "52") (name "/SWD") (class "Default")
      (node (ref "P1") (pin "3") (pinfunction "3_3") (pintype "passive"))
      (node (ref "U1") (pin "34") (pinfunction "PA13-SWD_34") (pintype "passive"))
    )
    (net (code "53") (name "/SWD1") (class "Default")
      (node (ref "*1") (pin "34") (pinfunction "PA13-SWD_34") (pintype "passive"))
      (node (ref "P9") (pin "3") (pinfunction "3_3") (pintype "passive"))
    )
    (net (code "54") (name "GND") (class "Default")
      (node (ref "C1") (pin "2") (pinfunction "2_2") (pintype "passive"))
      (node (ref "C15") (pin "2") (pinfunction "2_2") (pintype "passive"))
      (node (ref "C16") (pin "2") (pinfunction "2_2") (pintype "passive"))
      (node (ref "C17") (pin "2") (pinfunction "2_2") (pintype "passive"))
      (node (ref "C18") (pin "2") (pinfunction "2_2") (pintype "passive"))
      (node (ref "C19") (pin "2") (pinfunction "2_2") (pintype "passive"))
      (node (ref "C2") (pin "2") (pinfunction "2_2") (pintype "passive"))
      (node (ref "C20") (pin "2") (pinfunction "2_2") (pintype "passive"))
      (node (ref "C3") (pin "2") (pinfunction "2_2") (pintype "passive"))
      (node (ref "C4") (pin "2") (pinfunction "2_2") (pintype "passive"))
      (node (ref "C5") (pin "2") (pinfunction "2_2") (pintype "passive"))
      (node (ref "C6") (pin "2") (pinfunction "2_2") (pintype "passive"))
      (node (ref "L1") (pin "2") (pintype "passive"))
      (node (ref "P1") (pin "6") (pinfunction "6_6") (pintype "passive"))
      (node (ref "P1") (pin "8") (pinfunction "8_8") (pintype "passive"))
      (node (ref "P2") (pin "3") (pinfunction "3_3") (pintype "passive"))
      (node (ref "P3") (pin "10") (pinfunction "10_10") (pintype "passive"))
      (node (ref "P3") (pin "9") (pinfunction "9_9") (pintype "passive"))
      (node (ref "P4") (pin "6") (pinfunction "6_6") (pintype "passive"))
      (node (ref "R2") (pin "2") (pinfunction "2_2") (pintype "passive"))
      (node (ref "R4") (pin "1") (pinfunction "1_1") (pintype "passive"))
      (node (ref "U1") (pin "23") (pinfunction "VSS1_23") (pintype "passive"))
      (node (ref "U1") (pin "35") (pinfunction "VSS2_35") (pintype "passive"))
      (node (ref "U1") (pin "47") (pinfunction "VSS3_47") (pintype "passive"))
      (node (ref "U1") (pin "8") (pinfunction "VSSA_8") (pintype "passive"))
      (node (ref "q2") (pin "3") (pinfunction "S_3") (pintype "passive"))
      (node (ref "q4") (pin "3") (pinfunction "S_3") (pintype "passive"))
      (node (ref "t1") (pin "2") (pinfunction "2_2") (pintype "passive"))
      (node (ref "u2") (pin "3") (pinfunction "COM_3") (pintype "passive"))
      (node (ref "u3") (pin "3") (pinfunction "COM_3") (pintype "passive"))
      (node (ref "u4") (pin "1") (pinfunction "GND_1") (pintype "passive"))
      (node (ref "u5") (pin "1") (pinfunction "GND_1") (pintype "passive"))
      (node (ref "u6") (pin "7") (pinfunction "GND_7") (pintype "passive"))
    )
    (net (code "55") (name "GND1") (class "Default")
      (node (ref "*1") (pin "23") (pinfunction "VSS1_23") (pintype "passive"))
      (node (ref "*1") (pin "35") (pinfunction "VSS2_35") (pintype "passive"))
      (node (ref "*1") (pin "47") (pinfunction "VSS3_47") (pintype "passive"))
      (node (ref "*1") (pin "8") (pinfunction "VSSA_8") (pintype "passive"))
      (node (ref "*4") (pin "3") (pinfunction "S_3") (pintype "passive"))
      (node (ref "*5") (pin "2") (pintype "passive"))
      (node (ref "*6") (pin "1") (pinfunction "1_1") (pintype "passive"))
      (node (ref "*7") (pin "1") (pinfunction "GND_1") (pintype "passive"))
      (node (ref "*8") (pin "1") (pinfunction "GND_1") (pintype "passive"))
      (node (ref "C11") (pin "2") (pinfunction "2_2") (pintype "passive"))
      (node (ref "C12") (pin "2") (pinfunction "2_2") (pintype "passive"))
      (node (ref "C13") (pin "2") (pinfunction "2_2") (pintype "passive"))
      (node (ref "C14") (pin "2") (pinfunction "2_2") (pintype "passive"))
      (node (ref "C21") (pin "2") (pinfunction "2_2") (pintype "passive"))
      (node (ref "C22") (pin "2") (pinfunction "2_2") (pintype "passive"))
      (node (ref "C23") (pin "2") (pinfunction "2_2") (pintype "passive"))
      (node (ref "C24") (pin "2") (pinfunction "2_2") (pintype "passive"))
      (node (ref "C25") (pin "2") (pinfunction "2_2") (pintype "passive"))
      (node (ref "C26") (pin "2") (pinfunction "2_2") (pintype "passive"))
      (node (ref "C7") (pin "2") (pinfunction "2_2") (pintype "passive"))
      (node (ref "C9") (pin "2") (pinfunction "2_2") (pintype "passive"))
      (node (ref "P10") (pin "2") (pinfunction "2_2") (pintype "passive"))
      (node (ref "P11") (pin "4") (pinfunction "4_4") (pintype "passive"))
      (node (ref "P14") (pin "4") (pinfunction "4_4") (pintype "passive"))
      (node (ref "P6") (pin "10") (pinfunction "10_10") (pintype "passive"))
      (node (ref "P6") (pin "9") (pinfunction "9_9") (pintype "passive"))
      (node (ref "P7") (pin "10") (pinfunction "10_10") (pintype "passive"))
      (node (ref "P7") (pin "9") (pinfunction "9_9") (pintype "passive"))
      (node (ref "P8") (pin "10") (pinfunction "10_10") (pintype "passive"))
      (node (ref "P8") (pin "9") (pinfunction "9_9") (pintype "passive"))
      (node (ref "P9") (pin "6") (pinfunction "6_6") (pintype "passive"))
      (node (ref "P9") (pin "8") (pinfunction "8_8") (pintype "passive"))
      (node (ref "RT1") (pin "1") (pinfunction "1_1") (pintype "passive"))
      (node (ref "RT4") (pin "2") (pinfunction "2_2") (pintype "passive"))
      (node (ref "RT5") (pin "2") (pinfunction "2_2") (pintype "passive"))
    )
    (net (code "56") (name "Net-(*1-BOOT0)") (class "Default")
      (node (ref "*1") (pin "44") (pinfunction "BOOT0_44") (pintype "passive"))
      (node (ref "RT1") (pin "2") (pinfunction "2_2") (pintype "passive"))
    )
    (net (code "57") (name "Net-(*1-PD0-0SC)") (class "Default")
      (node (ref "*1") (pin "5") (pinfunction "PD0-0SC_5") (pintype "passive"))
      (node (ref "*2") (pin "1") (pinfunction "1_1") (pintype "passive"))
      (node (ref "C9") (pin "1") (pinfunction "1_1") (pintype "passive"))
    )
    (net (code "58") (name "Net-(*1-PD1-OSC)") (class "Default")
      (node (ref "*1") (pin "6") (pinfunction "PD1-OSC_6") (pintype "passive"))
      (node (ref "*2") (pin "2") (pinfunction "2_2") (pintype "passive"))
      (node (ref "C12") (pin "1") (pinfunction "1_1") (pintype "passive"))
    )
    (net (code "59") (name "Net-(*4-D)") (class "Default")
      (node (ref "*3") (pin "1") (pinfunction "1_1") (pintype "passive"))
      (node (ref "*4") (pin "2") (pinfunction "D_2") (pintype "passive"))
    )
    (net (code "60") (name "Net-(*4-G)") (class "Default")
      (node (ref "*4") (pin "1") (pinfunction "G_1") (pintype "passive"))
      (node (ref "ISO2") (pin "3") (pinfunction "Emitter_3") (pintype "passive"))
      (node (ref "RT5") (pin "1") (pinfunction "1_1") (pintype "passive"))
    )
    (net (code "61") (name "Net-(*5-Pad1)") (class "Default")
      (node (ref "*5") (pin "1") (pintype "passive"))
      (node (ref "RT3") (pin "1") (pinfunction "1_1") (pintype "passive"))
    )
    (net (code "62") (name "Net-(D1-A)") (class "Default")
      (node (ref "D1") (pin "1") (pinfunction "A_1") (pintype "passive"))
      (node (ref "R7") (pin "1") (pinfunction "1_1") (pintype "passive"))
      (node (ref "q1") (pin "1") (pinfunction "G_1") (pintype "passive"))
    )
    (net (code "63") (name "Net-(D1-K)") (class "Default")
      (node (ref "D1") (pin "2") (pinfunction "K_2") (pintype "passive"))
      (node (ref "R7") (pin "2") (pinfunction "2_2") (pintype "passive"))
      (node (ref "u2") (pin "7") (pinfunction "HD_7") (pintype "passive"))
    )
    (net (code "64") (name "Net-(ISO1-Anode)") (class "Default")
      (node (ref "ISO1") (pin "1") (pinfunction "Anode_1") (pintype "passive"))
      (node (ref "R1") (pin "2") (pinfunction "2_2") (pintype "passive"))
    )
    (net (code "65") (name "Net-(ISO1-Cathode)") (class "Default")
      (node (ref "ISO1") (pin "2") (pinfunction "Cathode_2") (pintype "passive"))
      (node (ref "P2") (pin "2") (pinfunction "2_2") (pintype "passive"))
      (node (ref "R5") (pin "1") (pinfunction "1_1") (pintype "passive"))
    )
    (net (code "66") (name "Net-(ISO2-Cathode)") (class "Default")
      (node (ref "ISO2") (pin "2") (pinfunction "Cathode_2") (pintype "passive"))
      (node (ref "RT4") (pin "1") (pinfunction "1_1") (pintype "passive"))
    )
    (net (code "67") (name "Net-(L1-Pad1)") (class "Default")
      (node (ref "L1") (pin "1") (pintype "passive"))
      (node (ref "R6") (pin "1") (pinfunction "1_1") (pintype "passive"))
    )
    (net (code "68") (name "Net-(P1-Pad2)") (class "Default")
      (node (ref "P1") (pin "2") (pinfunction "2_2") (pintype "passive"))
      (node (ref "R3") (pin "2") (pinfunction "2_2") (pintype "passive"))
    )
    (net (code "69") (name "Net-(P9-Pad2)") (class "Default")
      (node (ref "P9") (pin "2") (pinfunction "2_2") (pintype "passive"))
      (node (ref "RT2") (pin "1") (pinfunction "1_1") (pintype "passive"))
    )
    (net (code "70") (name "Net-(U1-BOOT0)") (class "Default")
      (node (ref "R2") (pin "1") (pinfunction "1_1") (pintype "passive"))
      (node (ref "U1") (pin "44") (pinfunction "BOOT0_44") (pintype "passive"))
    )
    (net (code "71") (name "Net-(U1-PD0-0SC)") (class "Default")
      (node (ref "C2") (pin "1") (pinfunction "1_1") (pintype "passive"))
      (node (ref "U1") (pin "5") (pinfunction "PD0-0SC_5") (pintype "passive"))
      (node (ref "Y1") (pin "1") (pinfunction "1_1") (pintype "passive"))
    )
    (net (code "72") (name "Net-(U1-PD1-OSC)") (class "Default")
      (node (ref "C4") (pin "1") (pinfunction "1_1") (pintype "passive"))
      (node (ref "U1") (pin "6") (pinfunction "PD1-OSC_6") (pintype "passive"))
      (node (ref "Y1") (pin "2") (pinfunction "2_2") (pintype "passive"))
    )
    (net (code "73") (name "Net-(c8-+)") (class "Default")
      (node (ref "c8") (pin "1") (pinfunction "+_1") (pintype "passive"))
      (node (ref "s1") (pin "2") (pinfunction "-_2") (pintype "passive"))
      (node (ref "u2") (pin "8") (pinfunction "VB_8") (pintype "passive"))
    )
    (net (code "74") (name "Net-(c10-+)") (class "Default")
      (node (ref "c10") (pin "1") (pinfunction "+_1") (pintype "passive"))
      (node (ref "s2") (pin "2") (pinfunction "-_2") (pintype "passive"))
      (node (ref "u3") (pin "8") (pinfunction "VB_8") (pintype "passive"))
    )
    (net (code "75") (name "Net-(d2-A)") (class "Default")
      (node (ref "R8") (pin "1") (pinfunction "1_1") (pintype "passive"))
      (node (ref "d2") (pin "1") (pinfunction "A_1") (pintype "passive"))
      (node (ref "q2") (pin "1") (pinfunction "G_1") (pintype "passive"))
    )
    (net (code "76") (name "Net-(d2-K)") (class "Default")
      (node (ref "R8") (pin "2") (pinfunction "2_2") (pintype "passive"))
      (node (ref "d2") (pin "2") (pinfunction "K_2") (pintype "passive"))
      (node (ref "u2") (pin "4") (pinfunction "LO_4") (pintype "passive"))
    )
    (net (code "77") (name "Net-(d3-A)") (class "Default")
      (node (ref "R9") (pin "1") (pinfunction "1_1") (pintype "passive"))
      (node (ref "d3") (pin "1") (pinfunction "A_1") (pintype "passive"))
      (node (ref "q3") (pin "1") (pinfunction "G_1") (pintype "passive"))
    )
    (net (code "78") (name "Net-(d3-K)") (class "Default")
      (node (ref "R9") (pin "2") (pinfunction "2_2") (pintype "passive"))
      (node (ref "d3") (pin "2") (pinfunction "K_2") (pintype "passive"))
      (node (ref "u3") (pin "7") (pinfunction "HD_7") (pintype "passive"))
    )
    (net (code "79") (name "Net-(d4-A)") (class "Default")
      (node (ref "R10") (pin "1") (pinfunction "1_1") (pintype "passive"))
      (node (ref "d4") (pin "1") (pinfunction "A_1") (pintype "passive"))
      (node (ref "q4") (pin "1") (pinfunction "G_1") (pintype "passive"))
    )
    (net (code "80") (name "Net-(d4-K)") (class "Default")
      (node (ref "R10") (pin "2") (pinfunction "2_2") (pintype "passive"))
      (node (ref "d4") (pin "2") (pinfunction "K_2") (pintype "passive"))
      (node (ref "u3") (pin "4") (pinfunction "LO_4") (pintype "passive"))
    )
    (net (code "81") (name "Net-(u6-1Y)") (class "Default")
      (node (ref "u6") (pin "1") (pinfunction "1Y_1") (pintype "passive"))
      (node (ref "u6") (pin "5") (pinfunction "2A_5") (pintype "passive"))
    )
    (net (code "82") (name "VCC") (class "Default")
      (node (ref "C1") (pin "1") (pinfunction "1_1") (pintype "passive"))
      (node (ref "C16") (pin "1") (pinfunction "1_1") (pintype "passive"))
      (node (ref "C18") (pin "1") (pinfunction "1_1") (pintype "passive"))
      (node (ref "C3") (pin "1") (pinfunction "1_1") (pintype "passive"))
      (node (ref "C5") (pin "1") (pinfunction "1_1") (pintype "passive"))
      (node (ref "C6") (pin "1") (pinfunction "1_1") (pintype "passive"))
      (node (ref "ISO1") (pin "4") (pinfunction "Collector_4") (pintype "passive"))
      (node (ref "P4") (pin "7") (pinfunction "7_7") (pintype "passive"))
      (node (ref "R3") (pin "1") (pinfunction "1_1") (pintype "passive"))
      (node (ref "R6") (pin "2") (pinfunction "2_2") (pintype "passive"))
      (node (ref "U1") (pin "24") (pinfunction "VDD1_24") (pintype "passive"))
      (node (ref "U1") (pin "36") (pinfunction "VDD2_36") (pintype "passive"))
      (node (ref "U1") (pin "48") (pinfunction "VDD3_48") (pintype "passive"))
      (node (ref "U1") (pin "9") (pinfunction "VDDA_9") (pintype "passive"))
      (node (ref "u5") (pin "2") (pinfunction "OUT_2") (pintype "passive"))
    )
    (net (code "83") (name "VCC1") (class "Default")
      (node (ref "*1") (pin "24") (pinfunction "VDD1_24") (pintype "passive"))
      (node (ref "*1") (pin "36") (pinfunction "VDD2_36") (pintype "passive"))
      (node (ref "*1") (pin "48") (pinfunction "VDD3_48") (pintype "passive"))
      (node (ref "*1") (pin "9") (pinfunction "VDDA_9") (pintype "passive"))
      (node (ref "*8") (pin "2") (pinfunction "OUT_2") (pintype "passive"))
      (node (ref "C11") (pin "1") (pinfunction "1_1") (pintype "passive"))
      (node (ref "C13") (pin "1") (pinfunction "1_1") (pintype "passive"))
      (node (ref "C14") (pin "1") (pinfunction "1_1") (pintype "passive"))
      (node (ref "C21") (pin "1") (pinfunction "1_1") (pintype "passive"))
      (node (ref "C22") (pin "1") (pinfunction "1_1") (pintype "passive"))
      (node (ref "C7") (pin "1") (pinfunction "1_1") (pintype "passive"))
      (node (ref "P10") (pin "1") (pinfunction "1_1") (pintype "passive"))
      (node (ref "P14") (pin "3") (pinfunction "3_3") (pintype "passive"))
      (node (ref "RT2") (pin "2") (pinfunction "2_2") (pintype "passive"))
      (node (ref "RT3") (pin "2") (pinfunction "2_2") (pintype "passive"))
    )
    (net (code "84") (name "unconnected-(*1-PA1-Pad11)") (class "Default")
      (node (ref "*1") (pin "11") (pinfunction "PA1_11") (pintype "passive"))
    )
    (net (code "85") (name "unconnected-(*1-PA11-Pad32)") (class "Default")
      (node (ref "*1") (pin "32") (pinfunction "PA11_32") (pintype "passive"))
    )
    (net (code "86") (name "unconnected-(*1-PA12-Pad33)") (class "Default")
      (node (ref "*1") (pin "33") (pinfunction "PA12_33") (pintype "passive"))
    )
    (net (code "87") (name "unconnected-(*1-PA15-Pad38)") (class "Default")
      (node (ref "*1") (pin "38") (pinfunction "PA15_38") (pintype "passive"))
    )
    (net (code "88") (name "unconnected-(*1-PB0-Pad18)") (class "Default")
      (node (ref "*1") (pin "18") (pinfunction "PB0_18") (pintype "passive"))
    )
    (net (code "89") (name "unconnected-(*1-PB1-Pad19)") (class "Default")
      (node (ref "*1") (pin "19") (pinfunction "PB1_19") (pintype "passive"))
    )
    (net (code "90") (name "unconnected-(*1-PB2-Pad20)") (class "Default")
      (node (ref "*1") (pin "20") (pinfunction "PB2_20") (pintype "passive"))
    )
    (net (code "91") (name "unconnected-(*1-PB8-Pad45)") (class "Default")
      (node (ref "*1") (pin "45") (pinfunction "PB8_45") (pintype "passive"))
    )
    (net (code "92") (name "unconnected-(*1-PB9-Pad46)") (class "Default")
      (node (ref "*1") (pin "46") (pinfunction "PB9_46") (pintype "passive"))
    )
    (net (code "93") (name "unconnected-(*1-PC13-Pad2)") (class "Default")
      (node (ref "*1") (pin "2") (pinfunction "PC13_2") (pintype "passive"))
    )
    (net (code "94") (name "unconnected-(*1-PC14-Pad3)") (class "Default")
      (node (ref "*1") (pin "3") (pinfunction "PC14_3") (pintype "passive"))
    )
    (net (code "95") (name "unconnected-(*1-PC15-Pad4)") (class "Default")
      (node (ref "*1") (pin "4") (pinfunction "PC15_4") (pintype "passive"))
    )
    (net (code "96") (name "unconnected-(*1-VBAT-Pad1)") (class "Default")
      (node (ref "*1") (pin "1") (pinfunction "VBAT_1") (pintype "passive"))
    )
    (net (code "97") (name "unconnected-(*7-NOP-Pad4)") (class "Default")
      (node (ref "*7") (pin "4") (pinfunction "NOP_4") (pintype "passive"))
    )
    (net (code "98") (name "unconnected-(*8-NOP-Pad4)") (class "Default")
      (node (ref "*8") (pin "4") (pinfunction "NOP_4") (pintype "passive"))
    )
    (net (code "99") (name "unconnected-(P1-Pad4)") (class "Default")
      (node (ref "P1") (pin "4") (pinfunction "4_4") (pintype "passive"))
    )
    (net (code "100") (name "unconnected-(P1-Pad7)") (class "Default")
      (node (ref "P1") (pin "7") (pinfunction "7_7") (pintype "passive"))
    )
    (net (code "101") (name "unconnected-(P1-Pad9)") (class "Default")
      (node (ref "P1") (pin "9") (pinfunction "9_9") (pintype "passive"))
    )
    (net (code "102") (name "unconnected-(P1-Pad10)") (class "Default")
      (node (ref "P1") (pin "10") (pinfunction "10_10") (pintype "passive"))
    )
    (net (code "103") (name "unconnected-(P9-Pad4)") (class "Default")
      (node (ref "P9") (pin "4") (pinfunction "4_4") (pintype "passive"))
    )
    (net (code "104") (name "unconnected-(P9-Pad7)") (class "Default")
      (node (ref "P9") (pin "7") (pinfunction "7_7") (pintype "passive"))
    )
    (net (code "105") (name "unconnected-(P9-Pad9)") (class "Default")
      (node (ref "P9") (pin "9") (pinfunction "9_9") (pintype "passive"))
    )
    (net (code "106") (name "unconnected-(P9-Pad10)") (class "Default")
      (node (ref "P9") (pin "10") (pinfunction "10_10") (pintype "passive"))
    )
    (net (code "107") (name "unconnected-(P11-Pad1)") (class "Default")
      (node (ref "P11") (pin "1") (pinfunction "1_1") (pintype "passive"))
    )
    (net (code "108") (name "unconnected-(P11-Pad5)") (class "Default")
      (node (ref "P11") (pin "5") (pinfunction "5_5") (pintype "passive"))
    )
    (net (code "109") (name "unconnected-(U1-PA1-Pad11)") (class "Default")
      (node (ref "U1") (pin "11") (pinfunction "PA1_11") (pintype "passive"))
    )
    (net (code "110") (name "unconnected-(U1-PA2-Pad12)") (class "Default")
      (node (ref "U1") (pin "12") (pinfunction "PA2_12") (pintype "passive"))
    )
    (net (code "111") (name "unconnected-(U1-PA3-Pad13)") (class "Default")
      (node (ref "U1") (pin "13") (pinfunction "PA3_13") (pintype "passive"))
    )
    (net (code "112") (name "unconnected-(U1-PA15-Pad38)") (class "Default")
      (node (ref "U1") (pin "38") (pinfunction "PA15_38") (pintype "passive"))
    )
    (net (code "113") (name "unconnected-(U1-PB0-Pad18)") (class "Default")
      (node (ref "U1") (pin "18") (pinfunction "PB0_18") (pintype "passive"))
    )
    (net (code "114") (name "unconnected-(U1-PB1-Pad19)") (class "Default")
      (node (ref "U1") (pin "19") (pinfunction "PB1_19") (pintype "passive"))
    )
    (net (code "115") (name "unconnected-(U1-PB2-Pad20)") (class "Default")
      (node (ref "U1") (pin "20") (pinfunction "PB2_20") (pintype "passive"))
    )
    (net (code "116") (name "unconnected-(U1-PB8-Pad45)") (class "Default")
      (node (ref "U1") (pin "45") (pinfunction "PB8_45") (pintype "passive"))
    )
    (net (code "117") (name "unconnected-(U1-PB9-Pad46)") (class "Default")
      (node (ref "U1") (pin "46") (pinfunction "PB9_46") (pintype "passive"))
    )
    (net (code "118") (name "unconnected-(U1-PB10-Pad21)") (class "Default")
      (node (ref "U1") (pin "21") (pinfunction "PB10_21") (pintype "passive"))
    )
    (net (code "119") (name "unconnected-(U1-PB11-Pad22)") (class "Default")
      (node (ref "U1") (pin "22") (pinfunction "PB11_22") (pintype "passive"))
    )
    (net (code "120") (name "unconnected-(U1-PB14-Pad27)") (class "Default")
      (node (ref "U1") (pin "27") (pinfunction "PB14_27") (pintype "passive"))
    )
    (net (code "121") (name "unconnected-(U1-PB15-Pad28)") (class "Default")
      (node (ref "U1") (pin "28") (pinfunction "PB15_28") (pintype "passive"))
    )
    (net (code "122") (name "unconnected-(U1-PC13-Pad2)") (class "Default")
      (node (ref "U1") (pin "2") (pinfunction "PC13_2") (pintype "passive"))
    )
    (net (code "123") (name "unconnected-(U1-PC14-Pad3)") (class "Default")
      (node (ref "U1") (pin "3") (pinfunction "PC14_3") (pintype "passive"))
    )
    (net (code "124") (name "unconnected-(U1-PC15-Pad4)") (class "Default")
      (node (ref "U1") (pin "4") (pinfunction "PC15_4") (pintype "passive"))
    )
    (net (code "125") (name "unconnected-(U1-VBAT-Pad1)") (class "Default")
      (node (ref "U1") (pin "1") (pinfunction "VBAT_1") (pintype "passive"))
    )
    (net (code "126") (name "unconnected-(u4-NOP-Pad4)") (class "Default")
      (node (ref "u4") (pin "4") (pinfunction "NOP_4") (pintype "passive"))
    )
    (net (code "127") (name "unconnected-(u5-NOP-Pad4)") (class "Default")
      (node (ref "u5") (pin "4") (pinfunction "NOP_4") (pintype "passive"))
    )
  )
)
